# M7065C.net
KiCad netlist of a schematic drawn in EAGLE
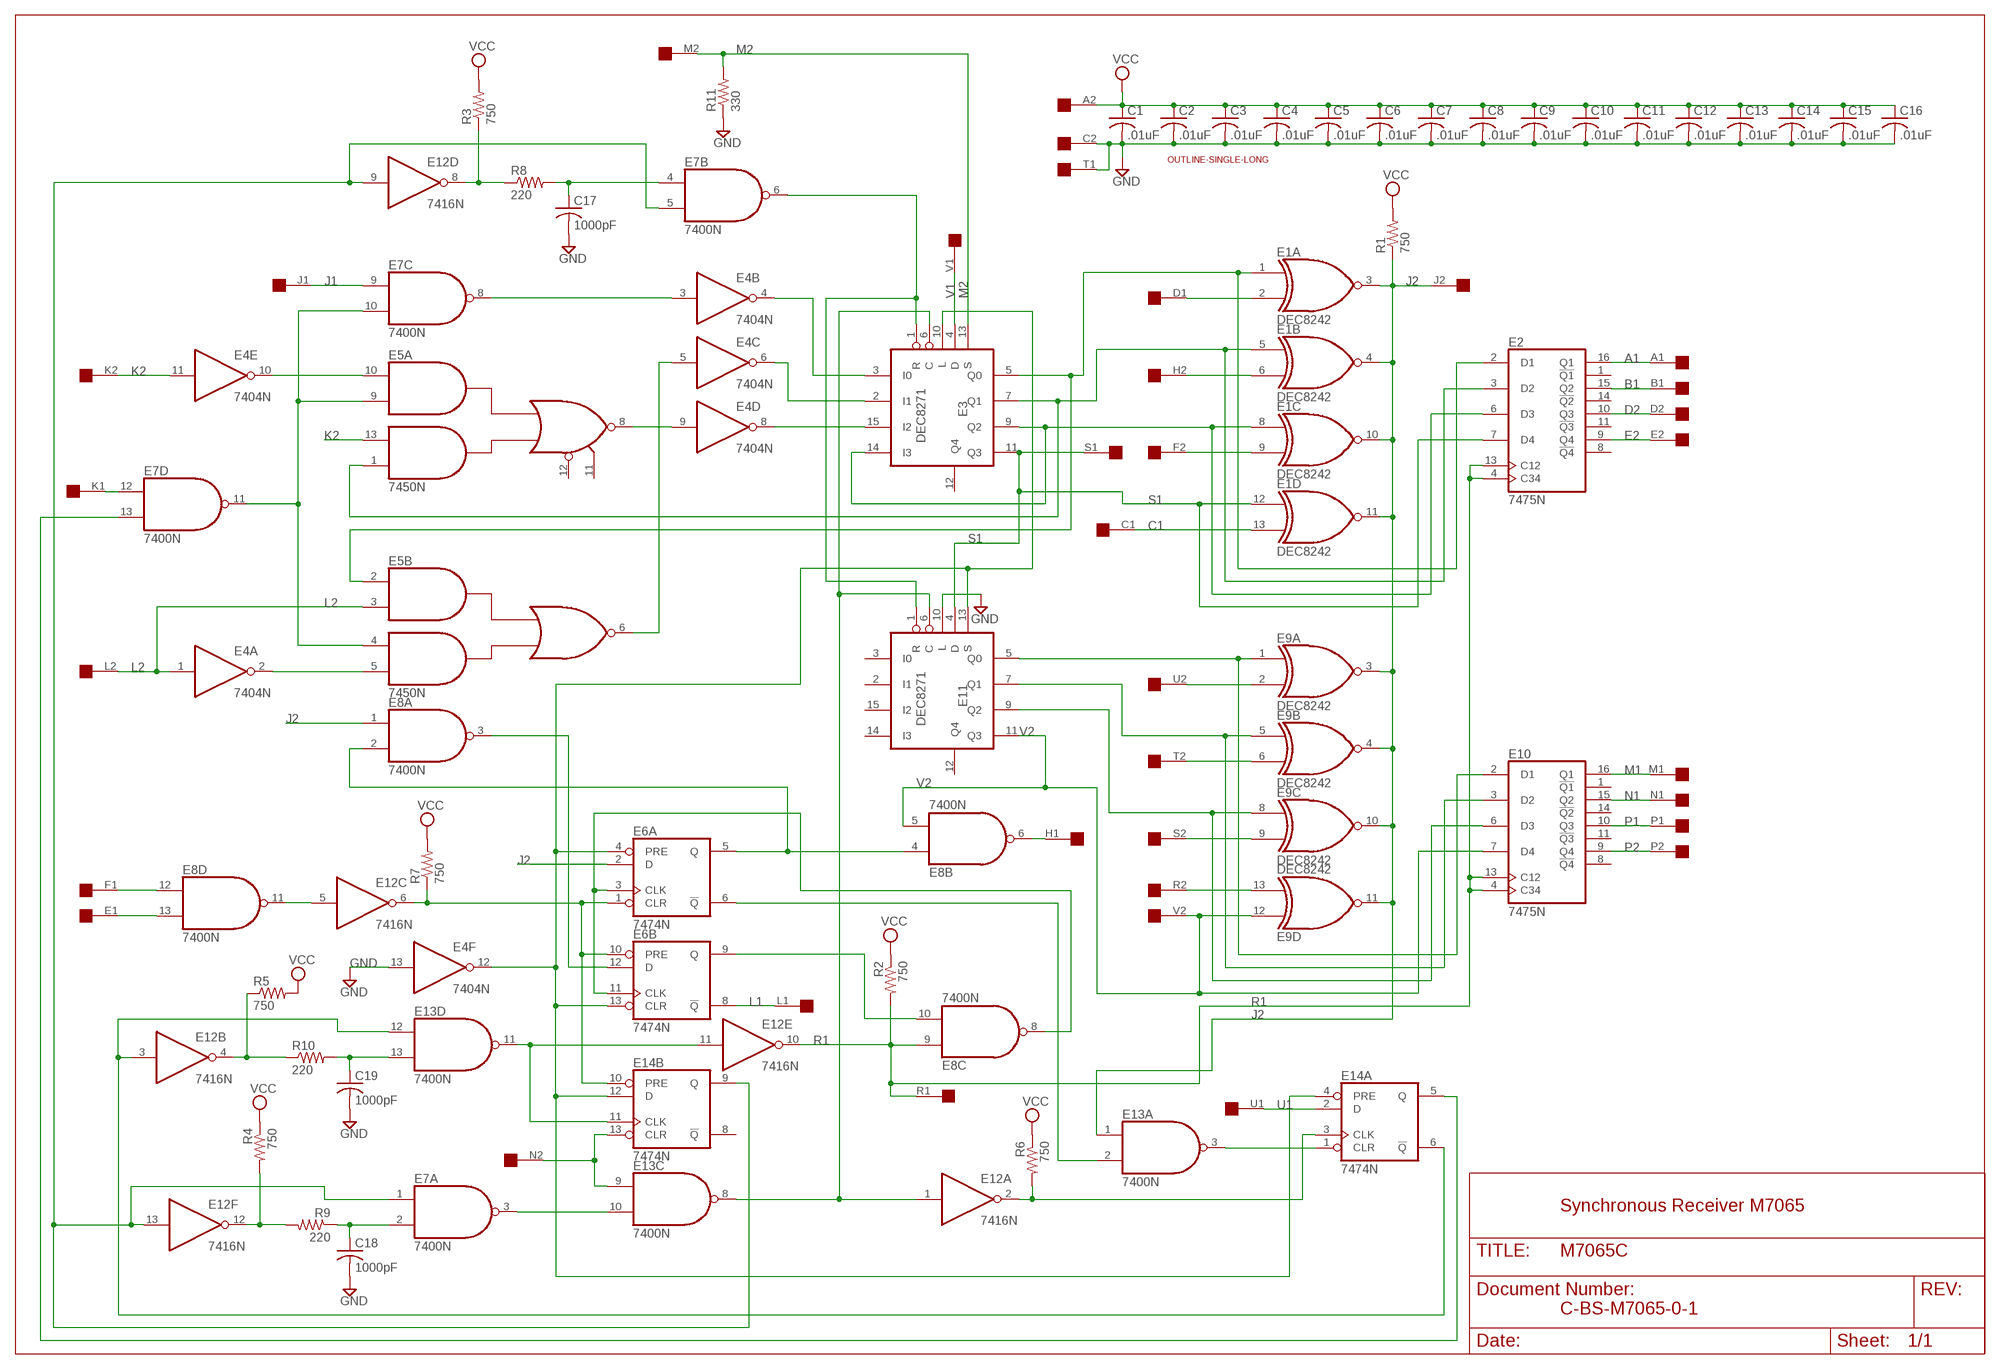
[diagram p0: schematic, sheet 1]

(export (version "E")
  (design (tool "Eeschema 10.0.6"))
  (components
    (comp (ref "C1")
      (value ".01uF")
      (footprint "eagle-import:C050-025X075")
      (libsource (lib "eagle-import") (part "C-US050-025X075"))
    )
    (comp (ref "C2")
      (value ".01uF")
      (footprint "eagle-import:C050-025X075")
      (libsource (lib "eagle-import") (part "C-US050-025X075"))
    )
    (comp (ref "C3")
      (value ".01uF")
      (footprint "eagle-import:C050-025X075")
      (libsource (lib "eagle-import") (part "C-US050-025X075"))
    )
    (comp (ref "C4")
      (value ".01uF")
      (footprint "eagle-import:C050-025X075")
      (libsource (lib "eagle-import") (part "C-US050-025X075"))
    )
    (comp (ref "C5")
      (value ".01uF")
      (footprint "eagle-import:C050-025X075")
      (libsource (lib "eagle-import") (part "C-US050-025X075"))
    )
    (comp (ref "C6")
      (value ".01uF")
      (footprint "eagle-import:C050-025X075")
      (libsource (lib "eagle-import") (part "C-US050-025X075"))
    )
    (comp (ref "C7")
      (value ".01uF")
      (footprint "eagle-import:C050-025X075")
      (libsource (lib "eagle-import") (part "C-US050-025X075"))
    )
    (comp (ref "C8")
      (value ".01uF")
      (footprint "eagle-import:C050-025X075")
      (libsource (lib "eagle-import") (part "C-US050-025X075"))
    )
    (comp (ref "C9")
      (value ".01uF")
      (footprint "eagle-import:C050-025X075")
      (libsource (lib "eagle-import") (part "C-US050-025X075"))
    )
    (comp (ref "C10")
      (value ".01uF")
      (footprint "eagle-import:C050-025X075")
      (libsource (lib "eagle-import") (part "C-US050-025X075"))
    )
    (comp (ref "C11")
      (value ".01uF")
      (footprint "eagle-import:C050-025X075")
      (libsource (lib "eagle-import") (part "C-US050-025X075"))
    )
    (comp (ref "C12")
      (value ".01uF")
      (footprint "eagle-import:C050-025X075")
      (libsource (lib "eagle-import") (part "C-US050-025X075"))
    )
    (comp (ref "C13")
      (value ".01uF")
      (footprint "eagle-import:C050-025X075")
      (libsource (lib "eagle-import") (part "C-US050-025X075"))
    )
    (comp (ref "C14")
      (value ".01uF")
      (footprint "eagle-import:C050-025X075")
      (libsource (lib "eagle-import") (part "C-US050-025X075"))
    )
    (comp (ref "C15")
      (value ".01uF")
      (footprint "eagle-import:C050-025X075")
      (libsource (lib "eagle-import") (part "C-US050-025X075"))
    )
    (comp (ref "C16")
      (value ".01uF")
      (footprint "eagle-import:C050-025X075")
      (libsource (lib "eagle-import") (part "C-US050-025X075"))
    )
    (comp (ref "C17")
      (value "1000pF")
      (footprint "eagle-import:C050-025X075")
      (libsource (lib "eagle-import") (part "C-US050-025X075"))
    )
    (comp (ref "C18")
      (value "1000pF")
      (footprint "eagle-import:C050-025X075")
      (libsource (lib "eagle-import") (part "C-US050-025X075"))
    )
    (comp (ref "C19")
      (value "1000pF")
      (footprint "eagle-import:C050-025X075")
      (libsource (lib "eagle-import") (part "C-US050-025X075"))
    )
    (comp (ref "E1")
      (value "DEC8242")
      (footprint "eagle-import:DIL14")
      (libsource (lib "eagle-import") (part "74266NLS"))
    )
    (comp (ref "E2")
      (value "7475N")
      (footprint "eagle-import:DIL16")
      (libsource (lib "eagle-import") (part "7475N"))
    )
    (comp (ref "E3")
      (value "DEC8271")
      (footprint "eagle-import:DIL16")
      (libsource (lib "eagle-import") (part "DEC8271"))
    )
    (comp (ref "E4")
      (value "7404N")
      (footprint "eagle-import:DIL14")
      (libsource (lib "eagle-import") (part "7404N"))
    )
    (comp (ref "E5")
      (value "7450N")
      (footprint "eagle-import:DIL14")
      (libsource (lib "eagle-import") (part "7450N"))
    )
    (comp (ref "E6")
      (value "7474N")
      (footprint "eagle-import:DIL14")
      (libsource (lib "eagle-import") (part "7474NS"))
    )
    (comp (ref "E7")
      (value "7400N")
      (footprint "eagle-import:DIL14")
      (libsource (lib "eagle-import") (part "7400N"))
    )
    (comp (ref "E8")
      (value "7400N")
      (footprint "eagle-import:DIL14")
      (libsource (lib "eagle-import") (part "7400N"))
    )
    (comp (ref "E9")
      (value "DEC8242")
      (footprint "eagle-import:DIL14")
      (libsource (lib "eagle-import") (part "74266NLS"))
    )
    (comp (ref "E10")
      (value "7475N")
      (footprint "eagle-import:DIL16")
      (libsource (lib "eagle-import") (part "7475N"))
    )
    (comp (ref "E11")
      (value "DEC8271")
      (footprint "eagle-import:DIL16")
      (libsource (lib "eagle-import") (part "DEC8271"))
    )
    (comp (ref "E12")
      (value "7416N")
      (footprint "eagle-import:DIL14")
      (libsource (lib "eagle-import") (part "7416N"))
    )
    (comp (ref "E13")
      (value "7400N")
      (footprint "eagle-import:DIL14")
      (libsource (lib "eagle-import") (part "7400N"))
    )
    (comp (ref "E14")
      (value "7474N")
      (footprint "eagle-import:DIL14")
      (libsource (lib "eagle-import") (part "7474NS"))
    )
    (comp (ref "R1")
      (value "750")
      (footprint "eagle-import:0207_10")
      (libsource (lib "eagle-import") (part "R-US_0207/10"))
    )
    (comp (ref "R2")
      (value "750")
      (footprint "eagle-import:0207_10")
      (libsource (lib "eagle-import") (part "R-US_0207/10"))
    )
    (comp (ref "R3")
      (value "750")
      (footprint "eagle-import:0207_10")
      (libsource (lib "eagle-import") (part "R-US_0207/10"))
    )
    (comp (ref "R4")
      (value "750")
      (footprint "eagle-import:0207_10")
      (libsource (lib "eagle-import") (part "R-US_0207/10"))
    )
    (comp (ref "R5")
      (value "750")
      (footprint "eagle-import:0207_10")
      (libsource (lib "eagle-import") (part "R-US_0207/10"))
    )
    (comp (ref "R6")
      (value "750")
      (footprint "eagle-import:0207_10")
      (libsource (lib "eagle-import") (part "R-US_0207/10"))
    )
    (comp (ref "R7")
      (value "750")
      (footprint "eagle-import:0207_10")
      (libsource (lib "eagle-import") (part "R-US_0207/10"))
    )
    (comp (ref "R8")
      (value "220")
      (footprint "eagle-import:0207_10")
      (libsource (lib "eagle-import") (part "R-US_0207/10"))
    )
    (comp (ref "R9")
      (value "220")
      (footprint "eagle-import:0207_10")
      (libsource (lib "eagle-import") (part "R-US_0207/10"))
    )
    (comp (ref "R10")
      (value "220")
      (footprint "eagle-import:0207_10")
      (libsource (lib "eagle-import") (part "R-US_0207/10"))
    )
    (comp (ref "R11")
      (value "330")
      (footprint "eagle-import:0207_10")
      (libsource (lib "eagle-import") (part "R-US_0207/10"))
    )
    (comp (ref "U$1")
      (value "OUTLINE-SINGLE-LONG")
      (footprint "eagle-import:SINGLE-LONG")
      (libsource (lib "eagle-import") (part "OUTLINE-SINGLE-LONG"))
    )
    (comp (ref "U$2")
      (value "SINGLE")
      (footprint "eagle-import:EDGE-CON2")
      (libsource (lib "eagle-import") (part "SINGLE"))
    )
  )
  (nets
    (net (code "1") (name "/A1") (class "Default")
      (node (ref "E2") (pin "16") (pinfunction "Q1_16") (pintype "output"))
      (node (ref "U$2") (pin "A1") (pinfunction "1_A1") (pintype "bidirectional"))
    )
    (net (code "2") (name "/B1") (class "Default")
      (node (ref "E2") (pin "15") (pinfunction "Q2_15") (pintype "output"))
      (node (ref "U$2") (pin "B1") (pinfunction "1_B1") (pintype "bidirectional"))
    )
    (net (code "3") (name "/C1") (class "Default")
      (node (ref "E1") (pin "13") (pinfunction "I1_13") (pintype "input"))
      (node (ref "U$2") (pin "C1") (pinfunction "1_C1") (pintype "bidirectional"))
    )
    (net (code "4") (name "/D2") (class "Default")
      (node (ref "E2") (pin "10") (pinfunction "Q3_10") (pintype "output"))
      (node (ref "U$2") (pin "D2") (pinfunction "1_D2") (pintype "bidirectional"))
    )
    (net (code "5") (name "/E2") (class "Default")
      (node (ref "E2") (pin "9") (pinfunction "Q4_9") (pintype "output"))
      (node (ref "U$2") (pin "E2") (pinfunction "1_E2") (pintype "bidirectional"))
    )
    (net (code "6") (name "/J1") (class "Default")
      (node (ref "E7") (pin "9") (pinfunction "I0_9") (pintype "input"))
      (node (ref "U$2") (pin "J1") (pinfunction "1_J1") (pintype "bidirectional"))
    )
    (net (code "7") (name "/J2") (class "Default")
      (node (ref "E1") (pin "10") (pinfunction "O_10") (pintype "open_collector"))
      (node (ref "E1") (pin "11") (pinfunction "O_11") (pintype "open_collector"))
      (node (ref "E1") (pin "3") (pinfunction "O_3") (pintype "open_collector"))
      (node (ref "E1") (pin "4") (pinfunction "O_4") (pintype "open_collector"))
      (node (ref "E13") (pin "1") (pinfunction "I0_1") (pintype "input"))
      (node (ref "E6") (pin "2") (pinfunction "D_2") (pintype "input"))
      (node (ref "E8") (pin "1") (pinfunction "I0_1") (pintype "input"))
      (node (ref "E9") (pin "10") (pinfunction "O_10") (pintype "open_collector"))
      (node (ref "E9") (pin "11") (pinfunction "O_11") (pintype "open_collector"))
      (node (ref "E9") (pin "3") (pinfunction "O_3") (pintype "open_collector"))
      (node (ref "E9") (pin "4") (pinfunction "O_4") (pintype "open_collector"))
      (node (ref "R1") (pin "1") (pinfunction "1_1") (pintype "passive"))
      (node (ref "U$2") (pin "J2") (pinfunction "1_J2") (pintype "bidirectional"))
    )
    (net (code "8") (name "/K2") (class "Default")
      (node (ref "E4") (pin "11") (pinfunction "I_11") (pintype "input"))
      (node (ref "E5") (pin "13") (pinfunction "I3_13") (pintype "input"))
      (node (ref "U$2") (pin "K2") (pinfunction "1_K2") (pintype "bidirectional"))
    )
    (net (code "9") (name "/L1") (class "Default")
      (node (ref "E6") (pin "8") (pinfunction "~{Q}_8") (pintype "output"))
      (node (ref "U$2") (pin "L1") (pinfunction "1_L1") (pintype "bidirectional"))
    )
    (net (code "10") (name "/L2") (class "Default")
      (node (ref "E4") (pin "1") (pinfunction "I_1") (pintype "input"))
      (node (ref "E5") (pin "3") (pinfunction "I2_3") (pintype "input"))
      (node (ref "U$2") (pin "L2") (pinfunction "1_L2") (pintype "bidirectional"))
    )
    (net (code "11") (name "/M1") (class "Default")
      (node (ref "E10") (pin "16") (pinfunction "Q1_16") (pintype "output"))
      (node (ref "U$2") (pin "M1") (pinfunction "1_M1") (pintype "bidirectional"))
    )
    (net (code "12") (name "/M2") (class "Default")
      (node (ref "E3") (pin "13") (pinfunction "S_13") (pintype "input"))
      (node (ref "R11") (pin "2") (pinfunction "2_2") (pintype "passive"))
      (node (ref "U$2") (pin "M2") (pinfunction "1_M2") (pintype "bidirectional"))
    )
    (net (code "13") (name "/N1") (class "Default")
      (node (ref "E10") (pin "15") (pinfunction "Q2_15") (pintype "output"))
      (node (ref "U$2") (pin "N1") (pinfunction "1_N1") (pintype "bidirectional"))
    )
    (net (code "14") (name "/P1") (class "Default")
      (node (ref "E10") (pin "10") (pinfunction "Q3_10") (pintype "output"))
      (node (ref "U$2") (pin "P1") (pinfunction "1_P1") (pintype "bidirectional"))
    )
    (net (code "15") (name "/P2") (class "Default")
      (node (ref "E10") (pin "9") (pinfunction "Q4_9") (pintype "output"))
      (node (ref "U$2") (pin "P2") (pinfunction "1_P2") (pintype "bidirectional"))
    )
    (net (code "16") (name "/R1") (class "Default")
      (node (ref "E10") (pin "13") (pinfunction "C12_13") (pintype "input"))
      (node (ref "E10") (pin "4") (pinfunction "C34_4") (pintype "input"))
      (node (ref "E12") (pin "10") (pinfunction "O_10") (pintype "open_collector"))
      (node (ref "E2") (pin "13") (pinfunction "C12_13") (pintype "input"))
      (node (ref "E2") (pin "4") (pinfunction "C34_4") (pintype "input"))
      (node (ref "E8") (pin "9") (pinfunction "I0_9") (pintype "input"))
      (node (ref "R2") (pin "2") (pinfunction "2_2") (pintype "passive"))
      (node (ref "U$2") (pin "R1") (pinfunction "1_R1") (pintype "bidirectional"))
    )
    (net (code "17") (name "/S1") (class "Default")
      (node (ref "E1") (pin "12") (pinfunction "I0_12") (pintype "input"))
      (node (ref "E11") (pin "4") (pinfunction "D_4") (pintype "input"))
      (node (ref "E2") (pin "7") (pinfunction "D4_7") (pintype "input"))
      (node (ref "E3") (pin "11") (pinfunction "Q3_11") (pintype "output"))
      (node (ref "U$2") (pin "S1") (pinfunction "1_S1") (pintype "bidirectional"))
    )
    (net (code "18") (name "/U1") (class "Default")
      (node (ref "E14") (pin "2") (pinfunction "D_2") (pintype "input"))
      (node (ref "U$2") (pin "U1") (pinfunction "1_U1") (pintype "bidirectional"))
    )
    (net (code "19") (name "/V1") (class "Default")
      (node (ref "E3") (pin "4") (pinfunction "D_4") (pintype "input"))
      (node (ref "U$2") (pin "V1") (pinfunction "1_V1") (pintype "bidirectional"))
    )
    (net (code "20") (name "/V2") (class "Default")
      (node (ref "E10") (pin "7") (pinfunction "D4_7") (pintype "input"))
      (node (ref "E11") (pin "11") (pinfunction "Q3_11") (pintype "output"))
      (node (ref "E8") (pin "5") (pinfunction "I1_5") (pintype "input"))
      (node (ref "E9") (pin "12") (pinfunction "I0_12") (pintype "input"))
      (node (ref "U$2") (pin "V2") (pinfunction "1_V2") (pintype "bidirectional"))
    )
    (net (code "21") (name "GND") (class "Default")
      (node (ref "C1") (pin "2") (pinfunction "2_2") (pintype "passive"))
      (node (ref "C10") (pin "2") (pinfunction "2_2") (pintype "passive"))
      (node (ref "C11") (pin "2") (pinfunction "2_2") (pintype "passive"))
      (node (ref "C12") (pin "2") (pinfunction "2_2") (pintype "passive"))
      (node (ref "C13") (pin "2") (pinfunction "2_2") (pintype "passive"))
      (node (ref "C14") (pin "2") (pinfunction "2_2") (pintype "passive"))
      (node (ref "C15") (pin "2") (pinfunction "2_2") (pintype "passive"))
      (node (ref "C16") (pin "2") (pinfunction "2_2") (pintype "passive"))
      (node (ref "C17") (pin "2") (pinfunction "2_2") (pintype "passive"))
      (node (ref "C18") (pin "2") (pinfunction "2_2") (pintype "passive"))
      (node (ref "C19") (pin "2") (pinfunction "2_2") (pintype "passive"))
      (node (ref "C2") (pin "2") (pinfunction "2_2") (pintype "passive"))
      (node (ref "C3") (pin "2") (pinfunction "2_2") (pintype "passive"))
      (node (ref "C4") (pin "2") (pinfunction "2_2") (pintype "passive"))
      (node (ref "C5") (pin "2") (pinfunction "2_2") (pintype "passive"))
      (node (ref "C6") (pin "2") (pinfunction "2_2") (pintype "passive"))
      (node (ref "C7") (pin "2") (pinfunction "2_2") (pintype "passive"))
      (node (ref "C8") (pin "2") (pinfunction "2_2") (pintype "passive"))
      (node (ref "C9") (pin "2") (pinfunction "2_2") (pintype "passive"))
      (node (ref "E11") (pin "10") (pinfunction "L_10") (pintype "input"))
      (node (ref "E4") (pin "13") (pinfunction "I_13") (pintype "input"))
      (node (ref "R11") (pin "1") (pinfunction "1_1") (pintype "passive"))
      (node (ref "U$2") (pin "C2") (pinfunction "1_C2") (pintype "bidirectional"))
      (node (ref "U$2") (pin "T1") (pinfunction "1_T1") (pintype "bidirectional"))
    )
    (net (code "22") (name "Net-(E1A-I0)") (class "Default")
      (node (ref "E1") (pin "1") (pinfunction "I0_1") (pintype "input"))
      (node (ref "E2") (pin "2") (pinfunction "D1_2") (pintype "input"))
      (node (ref "E3") (pin "5") (pinfunction "Q0_5") (pintype "output"))
      (node (ref "E5") (pin "2") (pinfunction "I1_2") (pintype "input"))
    )
    (net (code "23") (name "Net-(E1A-I1)") (class "Default")
      (node (ref "E1") (pin "2") (pinfunction "I1_2") (pintype "input"))
      (node (ref "U$2") (pin "D1") (pinfunction "1_D1") (pintype "bidirectional"))
    )
    (net (code "24") (name "Net-(E1B-I0)") (class "Default")
      (node (ref "E1") (pin "5") (pinfunction "I0_5") (pintype "input"))
      (node (ref "E2") (pin "3") (pinfunction "D2_3") (pintype "input"))
      (node (ref "E3") (pin "7") (pinfunction "Q1_7") (pintype "output"))
      (node (ref "E5") (pin "1") (pinfunction "I4_1") (pintype "input"))
    )
    (net (code "25") (name "Net-(E1B-I1)") (class "Default")
      (node (ref "E1") (pin "6") (pinfunction "I1_6") (pintype "input"))
      (node (ref "U$2") (pin "H2") (pinfunction "1_H2") (pintype "bidirectional"))
    )
    (net (code "26") (name "Net-(E1C-I0)") (class "Default")
      (node (ref "E1") (pin "8") (pinfunction "I0_8") (pintype "input"))
      (node (ref "E2") (pin "6") (pinfunction "D3_6") (pintype "input"))
      (node (ref "E3") (pin "14") (pinfunction "I3_14") (pintype "input"))
      (node (ref "E3") (pin "9") (pinfunction "Q2_9") (pintype "output"))
    )
    (net (code "27") (name "Net-(E1C-I1)") (class "Default")
      (node (ref "E1") (pin "9") (pinfunction "I1_9") (pintype "input"))
      (node (ref "U$2") (pin "F2") (pinfunction "1_F2") (pintype "bidirectional"))
    )
    (net (code "28") (name "Net-(E3A-I0)") (class "Default")
      (node (ref "E3") (pin "3") (pinfunction "I0_3") (pintype "input"))
      (node (ref "E4") (pin "4") (pinfunction "O_4") (pintype "output"))
    )
    (net (code "29") (name "Net-(E3A-I1)") (class "Default")
      (node (ref "E3") (pin "2") (pinfunction "I1_2") (pintype "input"))
      (node (ref "E4") (pin "6") (pinfunction "O_6") (pintype "output"))
    )
    (net (code "30") (name "Net-(E3A-I2)") (class "Default")
      (node (ref "E3") (pin "15") (pinfunction "I2_15") (pintype "input"))
      (node (ref "E4") (pin "8") (pinfunction "O_8") (pintype "output"))
    )
    (net (code "31") (name "Net-(E4A-O)") (class "Default")
      (node (ref "E4") (pin "2") (pinfunction "O_2") (pintype "output"))
      (node (ref "E5") (pin "5") (pinfunction "I4_5") (pintype "input"))
    )
    (net (code "32") (name "Net-(E4B-I)") (class "Default")
      (node (ref "E4") (pin "3") (pinfunction "I_3") (pintype "input"))
      (node (ref "E7") (pin "8") (pinfunction "O_8") (pintype "output"))
    )
    (net (code "33") (name "Net-(E4C-I)") (class "Default")
      (node (ref "E4") (pin "5") (pinfunction "I_5") (pintype "input"))
      (node (ref "E5") (pin "6") (pinfunction "O_6") (pintype "output"))
    )
    (net (code "34") (name "Net-(E4D-I)") (class "Default")
      (node (ref "E4") (pin "9") (pinfunction "I_9") (pintype "input"))
      (node (ref "E5") (pin "8") (pinfunction "O_8") (pintype "output"))
    )
    (net (code "35") (name "Net-(E4E-O)") (class "Default")
      (node (ref "E4") (pin "10") (pinfunction "O_10") (pintype "output"))
      (node (ref "E5") (pin "10") (pinfunction "I1_10") (pintype "input"))
    )
    (net (code "36") (name "Net-(E5A-I2)") (class "Default")
      (node (ref "E5") (pin "4") (pinfunction "I3_4") (pintype "input"))
      (node (ref "E5") (pin "9") (pinfunction "I2_9") (pintype "input"))
      (node (ref "E7") (pin "10") (pinfunction "I1_10") (pintype "input"))
      (node (ref "E7") (pin "11") (pinfunction "O_11") (pintype "output"))
    )
    (net (code "37") (name "Net-(E6A-CLK)") (class "Default")
      (node (ref "E6") (pin "11") (pinfunction "CLK_11") (pintype "input"))
      (node (ref "E6") (pin "3") (pinfunction "CLK_3") (pintype "input"))
      (node (ref "E8") (pin "8") (pinfunction "O_8") (pintype "output"))
    )
    (net (code "38") (name "Net-(E6A-Q)") (class "Default")
      (node (ref "E6") (pin "5") (pinfunction "Q_5") (pintype "output"))
      (node (ref "E8") (pin "2") (pinfunction "I1_2") (pintype "input"))
      (node (ref "E8") (pin "4") (pinfunction "I0_4") (pintype "input"))
    )
    (net (code "39") (name "Net-(E6B-D)") (class "Default")
      (node (ref "E6") (pin "12") (pinfunction "D_12") (pintype "input"))
      (node (ref "E8") (pin "3") (pinfunction "O_3") (pintype "output"))
    )
    (net (code "40") (name "Net-(E6B-Q)") (class "Default")
      (node (ref "E6") (pin "9") (pinfunction "Q_9") (pintype "output"))
      (node (ref "E8") (pin "10") (pinfunction "I1_10") (pintype "input"))
    )
    (net (code "41") (name "Net-(E7A-I1)") (class "Default")
      (node (ref "C18") (pin "1") (pinfunction "1_1") (pintype "passive"))
      (node (ref "E7") (pin "2") (pinfunction "I1_2") (pintype "input"))
      (node (ref "R9") (pin "1") (pinfunction "1_1") (pintype "passive"))
    )
    (net (code "42") (name "Net-(E7B-I0)") (class "Default")
      (node (ref "C17") (pin "1") (pinfunction "1_1") (pintype "passive"))
      (node (ref "E7") (pin "4") (pinfunction "I0_4") (pintype "input"))
      (node (ref "R8") (pin "2") (pinfunction "2_2") (pintype "passive"))
    )
    (net (code "43") (name "Net-(E7D-I0)") (class "Default")
      (node (ref "E7") (pin "12") (pinfunction "I0_12") (pintype "input"))
      (node (ref "U$2") (pin "K1") (pinfunction "1_K1") (pintype "bidirectional"))
    )
    (net (code "44") (name "Net-(E8B-O)") (class "Default")
      (node (ref "E8") (pin "6") (pinfunction "O_6") (pintype "output"))
      (node (ref "U$2") (pin "H1") (pinfunction "1_H1") (pintype "bidirectional"))
    )
    (net (code "45") (name "Net-(E8D-I0)") (class "Default")
      (node (ref "E8") (pin "12") (pinfunction "I0_12") (pintype "input"))
      (node (ref "U$2") (pin "F1") (pinfunction "1_F1") (pintype "bidirectional"))
    )
    (net (code "46") (name "Net-(E8D-I1)") (class "Default")
      (node (ref "E8") (pin "13") (pinfunction "I1_13") (pintype "input"))
      (node (ref "U$2") (pin "E1") (pinfunction "1_E1") (pintype "bidirectional"))
    )
    (net (code "47") (name "Net-(E9A-I1)") (class "Default")
      (node (ref "E9") (pin "2") (pinfunction "I1_2") (pintype "input"))
      (node (ref "U$2") (pin "U2") (pinfunction "1_U2") (pintype "bidirectional"))
    )
    (net (code "48") (name "Net-(E9B-I1)") (class "Default")
      (node (ref "E9") (pin "6") (pinfunction "I1_6") (pintype "input"))
      (node (ref "U$2") (pin "T2") (pinfunction "1_T2") (pintype "bidirectional"))
    )
    (net (code "49") (name "Net-(E9C-I1)") (class "Default")
      (node (ref "E9") (pin "9") (pinfunction "I1_9") (pintype "input"))
      (node (ref "U$2") (pin "S2") (pinfunction "1_S2") (pintype "bidirectional"))
    )
    (net (code "50") (name "Net-(E9D-I1)") (class "Default")
      (node (ref "E9") (pin "13") (pinfunction "I1_13") (pintype "input"))
      (node (ref "U$2") (pin "R2") (pinfunction "1_R2") (pintype "bidirectional"))
    )
    (net (code "51") (name "Net-(E10A-D1)") (class "Default")
      (node (ref "E10") (pin "2") (pinfunction "D1_2") (pintype "input"))
      (node (ref "E11") (pin "5") (pinfunction "Q0_5") (pintype "output"))
      (node (ref "E9") (pin "1") (pinfunction "I0_1") (pintype "input"))
    )
    (net (code "52") (name "Net-(E10A-D2)") (class "Default")
      (node (ref "E10") (pin "3") (pinfunction "D2_3") (pintype "input"))
      (node (ref "E11") (pin "7") (pinfunction "Q1_7") (pintype "output"))
      (node (ref "E9") (pin "5") (pinfunction "I0_5") (pintype "input"))
    )
    (net (code "53") (name "Net-(E10A-D3)") (class "Default")
      (node (ref "E10") (pin "6") (pinfunction "D3_6") (pintype "input"))
      (node (ref "E11") (pin "9") (pinfunction "Q2_9") (pintype "output"))
      (node (ref "E9") (pin "8") (pinfunction "I0_8") (pintype "input"))
    )
    (net (code "54") (name "Net-(E11A-C)") (class "Default")
      (node (ref "E11") (pin "6") (pinfunction "C_6") (pintype "input"))
      (node (ref "E12") (pin "1") (pinfunction "I_1") (pintype "input"))
      (node (ref "E13") (pin "8") (pinfunction "O_8") (pintype "output"))
      (node (ref "E3") (pin "6") (pinfunction "C_6") (pintype "input"))
    )
    (net (code "55") (name "Net-(E11A-R)") (class "Default")
      (node (ref "E11") (pin "1") (pinfunction "R_1") (pintype "input"))
      (node (ref "E3") (pin "1") (pinfunction "R_1") (pintype "input"))
      (node (ref "E7") (pin "6") (pinfunction "O_6") (pintype "output"))
    )
    (net (code "56") (name "Net-(E11A-S)") (class "Default")
      (node (ref "E11") (pin "13") (pinfunction "S_13") (pintype "input"))
      (node (ref "E14") (pin "12") (pinfunction "D_12") (pintype "input"))
      (node (ref "E14") (pin "4") (pinfunction "PRE_4") (pintype "input"))
      (node (ref "E3") (pin "10") (pinfunction "L_10") (pintype "input"))
      (node (ref "E4") (pin "12") (pinfunction "O_12") (pintype "output"))
      (node (ref "E6") (pin "13") (pinfunction "CLR_13") (pintype "input"))
      (node (ref "E6") (pin "4") (pinfunction "PRE_4") (pintype "input"))
    )
    (net (code "57") (name "Net-(E12A-O)") (class "Default")
      (node (ref "E12") (pin "2") (pinfunction "O_2") (pintype "open_collector"))
      (node (ref "E14") (pin "3") (pinfunction "CLK_3") (pintype "input"))
      (node (ref "R6") (pin "2") (pinfunction "2_2") (pintype "passive"))
    )
    (net (code "58") (name "Net-(E12B-I)") (class "Default")
      (node (ref "E12") (pin "3") (pinfunction "I_3") (pintype "input"))
      (node (ref "E13") (pin "12") (pinfunction "I0_12") (pintype "input"))
      (node (ref "E14") (pin "6") (pinfunction "~{Q}_6") (pintype "output"))
    )
    (net (code "59") (name "Net-(E12B-O)") (class "Default")
      (node (ref "E12") (pin "4") (pinfunction "O_4") (pintype "open_collector"))
      (node (ref "R10") (pin "1") (pinfunction "1_1") (pintype "passive"))
      (node (ref "R5") (pin "1") (pinfunction "1_1") (pintype "passive"))
    )
    (net (code "60") (name "Net-(E12C-I)") (class "Default")
      (node (ref "E12") (pin "5") (pinfunction "I_5") (pintype "input"))
      (node (ref "E8") (pin "11") (pinfunction "O_11") (pintype "output"))
    )
    (net (code "61") (name "Net-(E12C-O)") (class "Default")
      (node (ref "E12") (pin "6") (pinfunction "O_6") (pintype "open_collector"))
      (node (ref "E14") (pin "10") (pinfunction "PRE_10") (pintype "input"))
      (node (ref "E6") (pin "1") (pinfunction "CLR_1") (pintype "input"))
      (node (ref "E6") (pin "10") (pinfunction "PRE_10") (pintype "input"))
      (node (ref "R7") (pin "1") (pinfunction "1_1") (pintype "passive"))
    )
    (net (code "62") (name "Net-(E12D-I)") (class "Default")
      (node (ref "E12") (pin "13") (pinfunction "I_13") (pintype "input"))
      (node (ref "E12") (pin "9") (pinfunction "I_9") (pintype "input"))
      (node (ref "E14") (pin "9") (pinfunction "Q_9") (pintype "output"))
      (node (ref "E7") (pin "1") (pinfunction "I0_1") (pintype "input"))
      (node (ref "E7") (pin "5") (pinfunction "I1_5") (pintype "input"))
    )
    (net (code "63") (name "Net-(E12D-O)") (class "Default")
      (node (ref "E12") (pin "8") (pinfunction "O_8") (pintype "open_collector"))
      (node (ref "R3") (pin "1") (pinfunction "1_1") (pintype "passive"))
      (node (ref "R8") (pin "1") (pinfunction "1_1") (pintype "passive"))
    )
    (net (code "64") (name "Net-(E12E-I)") (class "Default")
      (node (ref "E12") (pin "11") (pinfunction "I_11") (pintype "input"))
      (node (ref "E13") (pin "11") (pinfunction "O_11") (pintype "output"))
      (node (ref "E14") (pin "11") (pinfunction "CLK_11") (pintype "input"))
    )
    (net (code "65") (name "Net-(E12F-O)") (class "Default")
      (node (ref "E12") (pin "12") (pinfunction "O_12") (pintype "open_collector"))
      (node (ref "R4") (pin "2") (pinfunction "2_2") (pintype "passive"))
      (node (ref "R9") (pin "2") (pinfunction "2_2") (pintype "passive"))
    )
    (net (code "66") (name "Net-(E13A-I1)") (class "Default")
      (node (ref "E13") (pin "2") (pinfunction "I1_2") (pintype "input"))
      (node (ref "E6") (pin "6") (pinfunction "~{Q}_6") (pintype "output"))
    )
    (net (code "67") (name "Net-(E13A-O)") (class "Default")
      (node (ref "E13") (pin "3") (pinfunction "O_3") (pintype "output"))
      (node (ref "E14") (pin "1") (pinfunction "CLR_1") (pintype "input"))
    )
    (net (code "68") (name "Net-(E13C-I0)") (class "Default")
      (node (ref "E13") (pin "9") (pinfunction "I0_9") (pintype "input"))
      (node (ref "E14") (pin "13") (pinfunction "CLR_13") (pintype "input"))
      (node (ref "U$2") (pin "N2") (pinfunction "1_N2") (pintype "bidirectional"))
    )
    (net (code "69") (name "Net-(E13C-I1)") (class "Default")
      (node (ref "E13") (pin "10") (pinfunction "I1_10") (pintype "input"))
      (node (ref "E7") (pin "3") (pinfunction "O_3") (pintype "output"))
    )
    (net (code "70") (name "Net-(E13D-I1)") (class "Default")
      (node (ref "C19") (pin "1") (pinfunction "1_1") (pintype "passive"))
      (node (ref "E13") (pin "13") (pinfunction "I1_13") (pintype "input"))
      (node (ref "R10") (pin "2") (pinfunction "2_2") (pintype "passive"))
    )
    (net (code "71") (name "Net-(E14A-Q)") (class "Default")
      (node (ref "E14") (pin "5") (pinfunction "Q_5") (pintype "output"))
      (node (ref "E7") (pin "13") (pinfunction "I1_13") (pintype "input"))
    )
    (net (code "72") (name "VCC") (class "Default")
      (node (ref "C1") (pin "1") (pinfunction "1_1") (pintype "passive"))
      (node (ref "C10") (pin "1") (pinfunction "1_1") (pintype "passive"))
      (node (ref "C11") (pin "1") (pinfunction "1_1") (pintype "passive"))
      (node (ref "C12") (pin "1") (pinfunction "1_1") (pintype "passive"))
      (node (ref "C13") (pin "1") (pinfunction "1_1") (pintype "passive"))
      (node (ref "C14") (pin "1") (pinfunction "1_1") (pintype "passive"))
      (node (ref "C15") (pin "1") (pinfunction "1_1") (pintype "passive"))
      (node (ref "C16") (pin "1") (pinfunction "1_1") (pintype "passive"))
      (node (ref "C2") (pin "1") (pinfunction "1_1") (pintype "passive"))
      (node (ref "C3") (pin "1") (pinfunction "1_1") (pintype "passive"))
      (node (ref "C4") (pin "1") (pinfunction "1_1") (pintype "passive"))
      (node (ref "C5") (pin "1") (pinfunction "1_1") (pintype "passive"))
      (node (ref "C6") (pin "1") (pinfunction "1_1") (pintype "passive"))
      (node (ref "C7") (pin "1") (pinfunction "1_1") (pintype "passive"))
      (node (ref "C8") (pin "1") (pinfunction "1_1") (pintype "passive"))
      (node (ref "C9") (pin "1") (pinfunction "1_1") (pintype "passive"))
      (node (ref "R1") (pin "2") (pinfunction "2_2") (pintype "passive"))
      (node (ref "R2") (pin "1") (pinfunction "1_1") (pintype "passive"))
      (node (ref "R3") (pin "2") (pinfunction "2_2") (pintype "passive"))
      (node (ref "R4") (pin "1") (pinfunction "1_1") (pintype "passive"))
      (node (ref "R5") (pin "2") (pinfunction "2_2") (pintype "passive"))
      (node (ref "R6") (pin "1") (pinfunction "1_1") (pintype "passive"))
      (node (ref "R7") (pin "2") (pinfunction "2_2") (pintype "passive"))
      (node (ref "U$2") (pin "A2") (pinfunction "1_A2") (pintype "bidirectional"))
    )
    (net (code "73") (name "unconnected-(E2A-~{Q1}-Pad1)") (class "Default")
      (node (ref "E2") (pin "1") (pinfunction "~{Q1}_1") (pintype "output"))
    )
    (net (code "74") (name "unconnected-(E2A-~{Q2}-Pad14)") (class "Default")
      (node (ref "E2") (pin "14") (pinfunction "~{Q2}_14") (pintype "output"))
    )
    (net (code "75") (name "unconnected-(E2A-~{Q3}-Pad11)") (class "Default")
      (node (ref "E2") (pin "11") (pinfunction "~{Q3}_11") (pintype "output"))
    )
    (net (code "76") (name "unconnected-(E2A-~{Q4}-Pad8)") (class "Default")
      (node (ref "E2") (pin "8") (pinfunction "~{Q4}_8") (pintype "output"))
    )
    (net (code "77") (name "unconnected-(E3A-Q4-Pad12)") (class "Default")
      (node (ref "E3") (pin "12") (pinfunction "Q4_12") (pintype "output"))
    )
    (net (code "78") (name "unconnected-(E5A-I5-Pad12)") (class "Default")
      (node (ref "E5") (pin "12") (pinfunction "I5_12") (pintype "passive"))
    )
    (net (code "79") (name "unconnected-(E5A-I6-Pad11)") (class "Default")
      (node (ref "E5") (pin "11") (pinfunction "I6_11") (pintype "passive"))
    )
    (net (code "80") (name "unconnected-(E10A-~{Q1}-Pad1)") (class "Default")
      (node (ref "E10") (pin "1") (pinfunction "~{Q1}_1") (pintype "output"))
    )
    (net (code "81") (name "unconnected-(E10A-~{Q2}-Pad14)") (class "Default")
      (node (ref "E10") (pin "14") (pinfunction "~{Q2}_14") (pintype "output"))
    )
    (net (code "82") (name "unconnected-(E10A-~{Q3}-Pad11)") (class "Default")
      (node (ref "E10") (pin "11") (pinfunction "~{Q3}_11") (pintype "output"))
    )
    (net (code "83") (name "unconnected-(E10A-~{Q4}-Pad8)") (class "Default")
      (node (ref "E10") (pin "8") (pinfunction "~{Q4}_8") (pintype "output"))
    )
    (net (code "84") (name "unconnected-(E11A-I0-Pad3)") (class "Default")
      (node (ref "E11") (pin "3") (pinfunction "I0_3") (pintype "input"))
    )
    (net (code "85") (name "unconnected-(E11A-I1-Pad2)") (class "Default")
      (node (ref "E11") (pin "2") (pinfunction "I1_2") (pintype "input"))
    )
    (net (code "86") (name "unconnected-(E11A-I2-Pad15)") (class "Default")
      (node (ref "E11") (pin "15") (pinfunction "I2_15") (pintype "input"))
    )
    (net (code "87") (name "unconnected-(E11A-I3-Pad14)") (class "Default")
      (node (ref "E11") (pin "14") (pinfunction "I3_14") (pintype "input"))
    )
    (net (code "88") (name "unconnected-(E11A-Q4-Pad12)") (class "Default")
      (node (ref "E11") (pin "12") (pinfunction "Q4_12") (pintype "output"))
    )
    (net (code "89") (name "unconnected-(E14B-~{Q}-Pad8)") (class "Default")
      (node (ref "E14") (pin "8") (pinfunction "~{Q}_8") (pintype "output"))
    )
  )
)
